# voltage.net
KiCad netlist of a schematic drawn in EAGLE
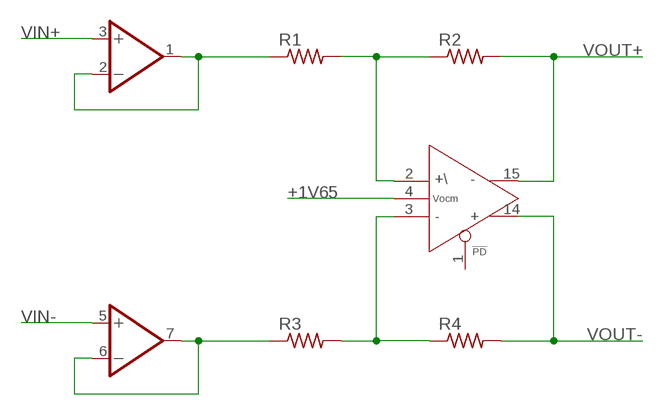
[diagram p0: schematic, sheet 1]

(export (version "E")
  (design (tool "Eeschema 10.0.6"))
  (components
    (comp (ref "R1")
      (value "R-US_R0805")
      (footprint "eagle-import:R0805")
      (libsource (lib "eagle-import") (part "R-US_R0805"))
    )
    (comp (ref "R2")
      (value "R-US_R0805")
      (footprint "eagle-import:R0805")
      (libsource (lib "eagle-import") (part "R-US_R0805"))
    )
    (comp (ref "R3")
      (value "R-US_R0805")
      (footprint "eagle-import:R0805")
      (libsource (lib "eagle-import") (part "R-US_R0805"))
    )
    (comp (ref "R4")
      (value "R-US_R0805")
      (footprint "eagle-import:R0805")
      (libsource (lib "eagle-import") (part "R-US_R0805"))
    )
    (comp (ref "U1")
      (value "THS4532IPW")
      (footprint "eagle-import:SOP65P640X120-16N")
      (fields
        (field (name "DIGI-KEY_PART_NUMBER") "296-39813-5-ND")
        (field (name "MF") "Texas Instruments")
        (field (name "SPICEPREFIX") "X")
      )
      (libsource (lib "eagle-import") (part "THS4532IPW"))
    )
    (comp (ref "U2")
      (value "MAX9944ATA+T")
      (footprint "eagle-import:21-0137_T833+2_MXM")
      (fields (field (name "COPYRIGHT") "Copyright (C) 2023 Ultra Librarian. All rights reserved."))
      (libsource (lib "eagle-import") (part "MAX9944ATA+T"))
    )
  )
  (nets
    (net (code "1") (name "/+1V65") (class "Default")
      (node (ref "U1") (pin "4") (pinfunction "VOCM_4") (pintype "passive"))
    )
    (net (code "2") (name "/VIN+") (class "Default")
      (node (ref "U2") (pin "3") (pinfunction "+IN_3") (pintype "input"))
    )
    (net (code "3") (name "/VIN-") (class "Default")
      (node (ref "U2") (pin "5") (pinfunction "+IN_5") (pintype "input"))
    )
    (net (code "4") (name "/VOUT+") (class "Default")
      (node (ref "R2") (pin "2") (pinfunction "2_2") (pintype "passive"))
      (node (ref "U1") (pin "15") (pinfunction "OUT-_15") (pintype "output"))
    )
    (net (code "5") (name "/VOUT-") (class "Default")
      (node (ref "R4") (pin "2") (pinfunction "2_2") (pintype "passive"))
      (node (ref "U1") (pin "14") (pinfunction "OUT+_14") (pintype "output"))
    )
    (net (code "6") (name "Net-(U1A-+IN)") (class "Default")
      (node (ref "R1") (pin "2") (pinfunction "2_2") (pintype "passive"))
      (node (ref "R2") (pin "1") (pinfunction "1_1") (pintype "passive"))
      (node (ref "U1") (pin "2") (pinfunction "+IN_2") (pintype "input"))
    )
    (net (code "7") (name "Net-(U1A--IN)") (class "Default")
      (node (ref "R3") (pin "2") (pinfunction "2_2") (pintype "passive"))
      (node (ref "R4") (pin "1") (pinfunction "1_1") (pintype "passive"))
      (node (ref "U1") (pin "3") (pinfunction "-IN_3") (pintype "input"))
    )
    (net (code "8") (name "Net-(U2A--IN)") (class "Default")
      (node (ref "R1") (pin "1") (pinfunction "1_1") (pintype "passive"))
      (node (ref "U2") (pin "1") (pinfunction "OUT_1") (pintype "output"))
      (node (ref "U2") (pin "2") (pinfunction "-IN_2") (pintype "input"))
    )
    (net (code "9") (name "Net-(U2B--IN)") (class "Default")
      (node (ref "R3") (pin "1") (pinfunction "1_1") (pintype "passive"))
      (node (ref "U2") (pin "6") (pinfunction "-IN_6") (pintype "input"))
      (node (ref "U2") (pin "7") (pinfunction "OUT_7") (pintype "output"))
    )
    (net (code "10") (name "unconnected-(U1A-~{PD}-Pad1)") (class "Default")
      (node (ref "U1") (pin "1") (pinfunction "~{PD}_1") (pintype "passive"))
    )
  )
)
